# Display-Board_Rack-PDU_3_0.net
KiCad netlist of a schematic drawn in EAGLE
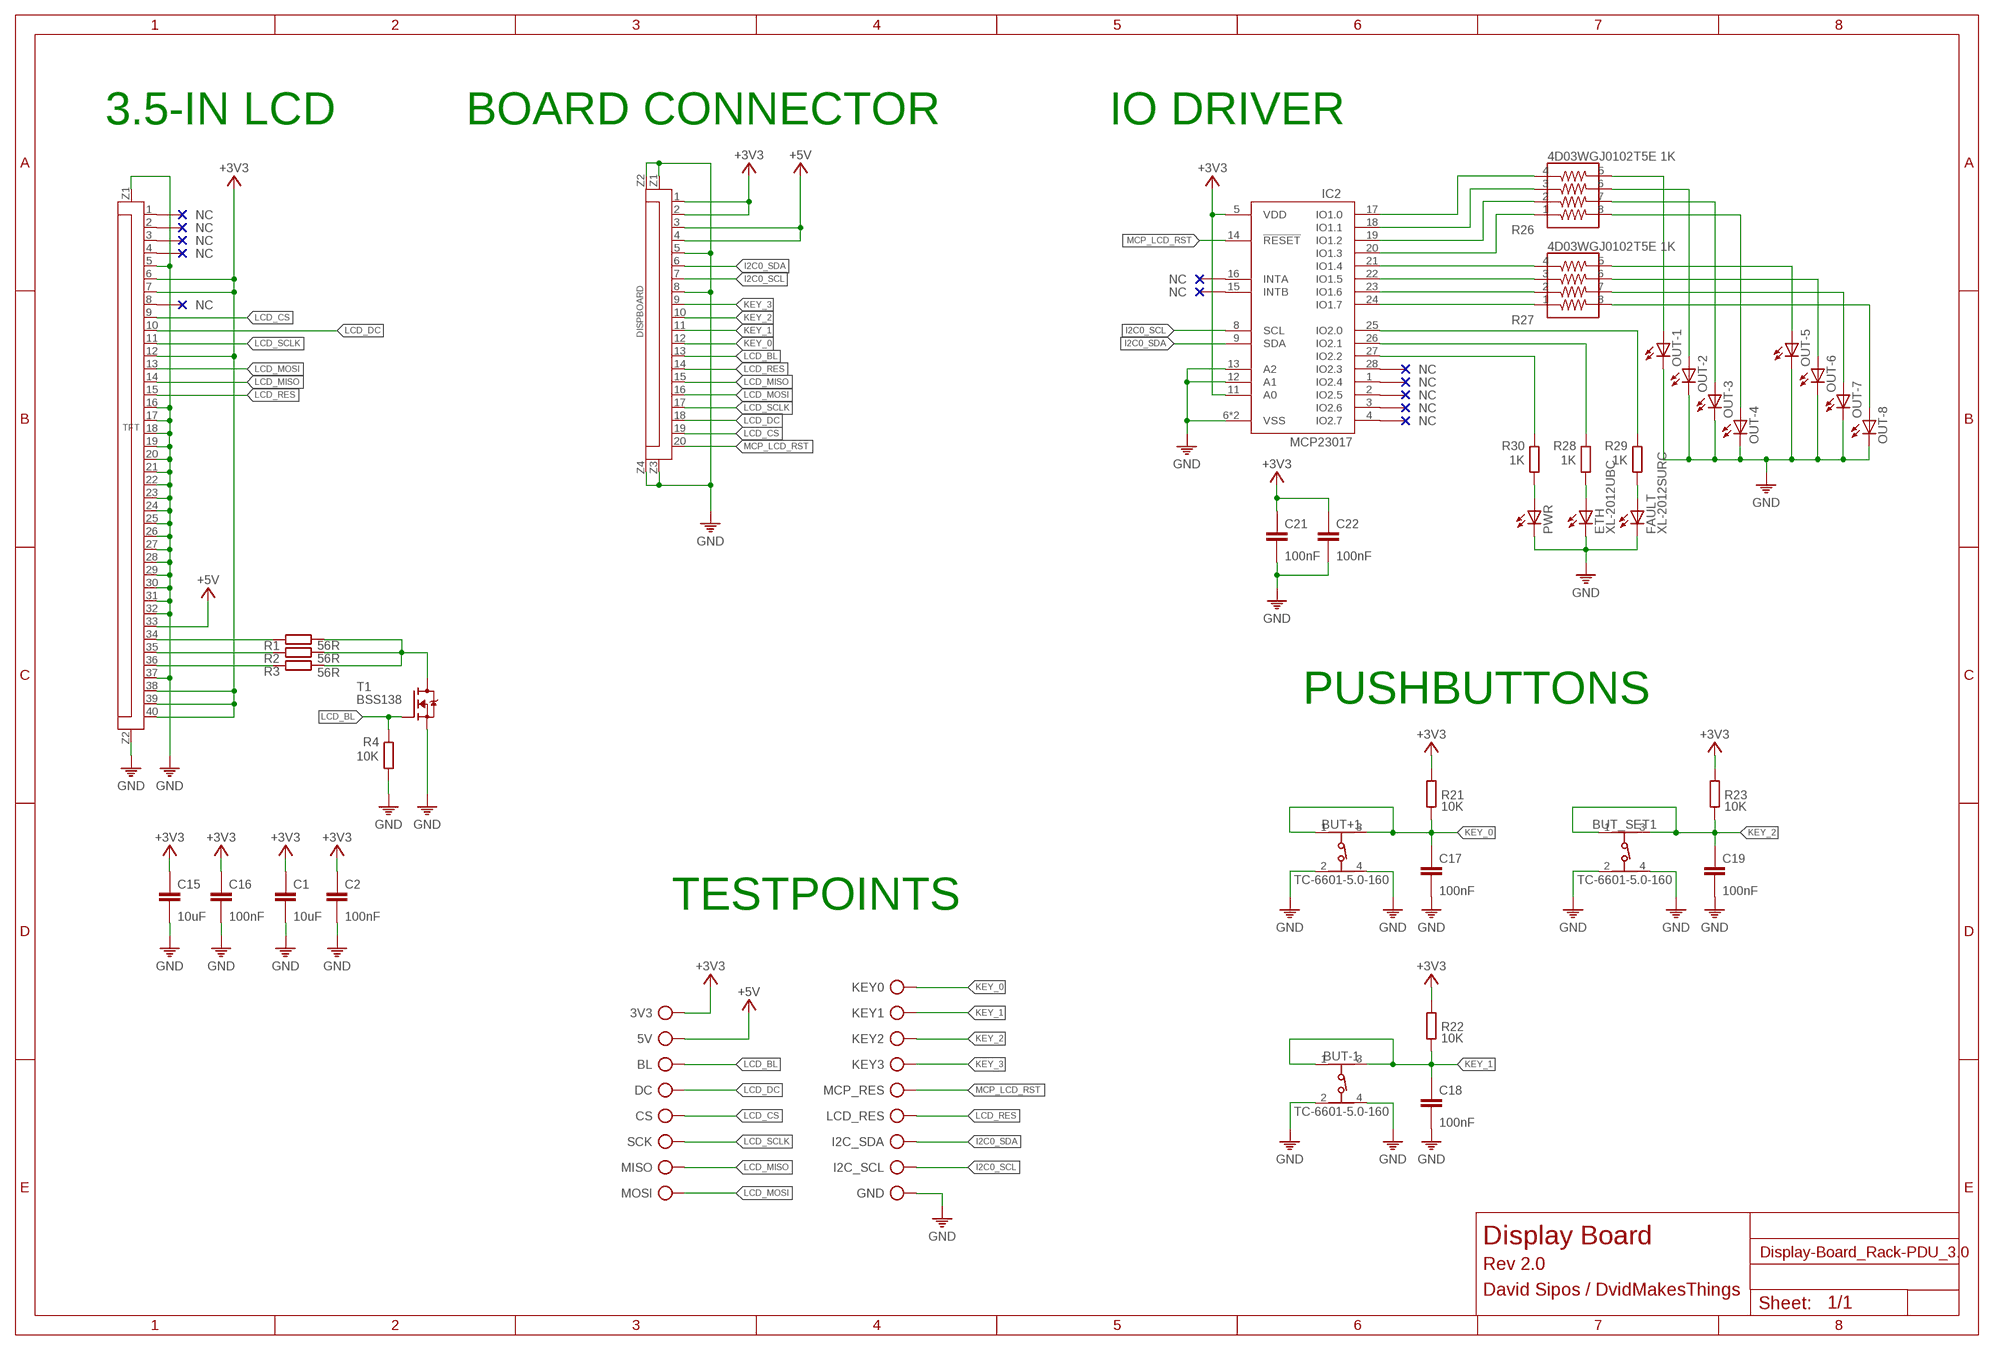
[diagram p0: schematic, sheet 1]

(export (version "E")
  (design (tool "Eeschema 10.0.6"))
  (components
    (comp (ref "3V3") (value "TP") (footprint "eagle-import:TP") (libsource (lib "eagle-import") (part "TP")))
    (comp (ref "5V") (value "TP") (footprint "eagle-import:TP") (libsource (lib "eagle-import") (part "TP")))
    (comp (ref "BL") (value "TP") (footprint "eagle-import:TP") (libsource (lib "eagle-import") (part "TP")))
    (comp (ref "BUT+1")
      (value "TC-6601-5.0-160")
      (footprint "eagle-import:430182043816")
      (libsource (lib "eagle-import") (part "430182043816"))
    )
    (comp (ref "BUT-1")
      (value "TC-6601-5.0-160")
      (footprint "eagle-import:430182043816")
      (libsource (lib "eagle-import") (part "430182043816"))
    )
    (comp (ref "BUT_SET1")
      (value "TC-6601-5.0-160")
      (footprint "eagle-import:430182043816")
      (libsource (lib "eagle-import") (part "430182043816"))
    )
    (comp (ref "C1")
      (value "10uF")
      (footprint "eagle-import:C0402")
      (libsource (lib "eagle-import") (part "C-0402"))
    )
    (comp (ref "C2")
      (value "100nF")
      (footprint "eagle-import:C0402")
      (libsource (lib "eagle-import") (part "C-0402"))
    )
    (comp (ref "C15")
      (value "10uF")
      (footprint "eagle-import:C0402")
      (libsource (lib "eagle-import") (part "C-0402"))
    )
    (comp (ref "C16")
      (value "100nF")
      (footprint "eagle-import:C0402")
      (libsource (lib "eagle-import") (part "C-0402"))
    )
    (comp (ref "C17")
      (value "100nF")
      (footprint "eagle-import:C0402")
      (libsource (lib "eagle-import") (part "C-0402"))
    )
    (comp (ref "C18")
      (value "100nF")
      (footprint "eagle-import:C0402")
      (libsource (lib "eagle-import") (part "C-0402"))
    )
    (comp (ref "C19")
      (value "100nF")
      (footprint "eagle-import:C0402")
      (libsource (lib "eagle-import") (part "C-0402"))
    )
    (comp (ref "C21")
      (value "100nF")
      (footprint "eagle-import:C0402")
      (libsource (lib "eagle-import") (part "C-0402"))
    )
    (comp (ref "C22")
      (value "100nF")
      (footprint "eagle-import:C0402")
      (libsource (lib "eagle-import") (part "C-0402"))
    )
    (comp (ref "CS") (value "TP") (footprint "eagle-import:TP") (libsource (lib "eagle-import") (part "TP")))
    (comp (ref "DC") (value "TP") (footprint "eagle-import:TP") (libsource (lib "eagle-import") (part "TP")))
    (comp (ref "DISPBOARD")
      (value "FPC20-H")
      (footprint "eagle-import:FPC20")
      (libsource (lib "eagle-import") (part "FPC20-H"))
    )
    (comp (ref "ETH")
      (value "XL-2012UBC")
      (footprint "eagle-import:CHIP-LED0805")
      (libsource (lib "eagle-import") (part "LEDCHIP-LED0805"))
    )
    (comp (ref "FAULT")
      (value "XL-2012SURC")
      (footprint "eagle-import:CHIP-LED0805")
      (libsource (lib "eagle-import") (part "LEDCHIP-LED0805"))
    )
    (comp (ref "GND") (value "TP") (footprint "eagle-import:TP") (libsource (lib "eagle-import") (part "TP")))
    (comp (ref "I2C_SCL")
      (value "TP")
      (footprint "eagle-import:TP")
      (libsource (lib "eagle-import") (part "TP"))
    )
    (comp (ref "I2C_SDA")
      (value "TP")
      (footprint "eagle-import:TP")
      (libsource (lib "eagle-import") (part "TP"))
    )
    (comp (ref "IC2")
      (value "MCP23017-E/ML")
      (footprint "eagle-import:QFN28[6X6]ML")
      (libsource (lib "eagle-import") (part "MCP23017-E/ML"))
    )
    (comp (ref "KEY0")
      (value "TP")
      (footprint "eagle-import:TP")
      (libsource (lib "eagle-import") (part "TP"))
    )
    (comp (ref "KEY1")
      (value "TP")
      (footprint "eagle-import:TP")
      (libsource (lib "eagle-import") (part "TP"))
    )
    (comp (ref "KEY2")
      (value "TP")
      (footprint "eagle-import:TP")
      (libsource (lib "eagle-import") (part "TP"))
    )
    (comp (ref "KEY3")
      (value "TP")
      (footprint "eagle-import:TP")
      (libsource (lib "eagle-import") (part "TP"))
    )
    (comp (ref "LCD_RES")
      (value "TP")
      (footprint "eagle-import:TP")
      (libsource (lib "eagle-import") (part "TP"))
    )
    (comp (ref "MCP_RES")
      (value "TP")
      (footprint "eagle-import:TP")
      (libsource (lib "eagle-import") (part "TP"))
    )
    (comp (ref "MISO")
      (value "TP")
      (footprint "eagle-import:TP")
      (libsource (lib "eagle-import") (part "TP"))
    )
    (comp (ref "MOSI")
      (value "TP")
      (footprint "eagle-import:TP")
      (libsource (lib "eagle-import") (part "TP"))
    )
    (comp (ref "OUT-1")
      (value "LEDCHIP-LED0805")
      (footprint "eagle-import:CHIP-LED0805")
      (libsource (lib "eagle-import") (part "LEDCHIP-LED0805"))
    )
    (comp (ref "OUT-2")
      (value "LEDCHIP-LED0805")
      (footprint "eagle-import:CHIP-LED0805")
      (libsource (lib "eagle-import") (part "LEDCHIP-LED0805"))
    )
    (comp (ref "OUT-3")
      (value "LEDCHIP-LED0805")
      (footprint "eagle-import:CHIP-LED0805")
      (libsource (lib "eagle-import") (part "LEDCHIP-LED0805"))
    )
    (comp (ref "OUT-4")
      (value "LEDCHIP-LED0805")
      (footprint "eagle-import:CHIP-LED0805")
      (libsource (lib "eagle-import") (part "LEDCHIP-LED0805"))
    )
    (comp (ref "OUT-5")
      (value "LEDCHIP-LED0805")
      (footprint "eagle-import:CHIP-LED0805")
      (libsource (lib "eagle-import") (part "LEDCHIP-LED0805"))
    )
    (comp (ref "OUT-6")
      (value "LEDCHIP-LED0805")
      (footprint "eagle-import:CHIP-LED0805")
      (libsource (lib "eagle-import") (part "LEDCHIP-LED0805"))
    )
    (comp (ref "OUT-7")
      (value "LEDCHIP-LED0805")
      (footprint "eagle-import:CHIP-LED0805")
      (libsource (lib "eagle-import") (part "LEDCHIP-LED0805"))
    )
    (comp (ref "OUT-8")
      (value "LEDCHIP-LED0805")
      (footprint "eagle-import:CHIP-LED0805")
      (libsource (lib "eagle-import") (part "LEDCHIP-LED0805"))
    )
    (comp (ref "PWR")
      (value "LEDCHIP-LED0805")
      (footprint "eagle-import:CHIP-LED0805")
      (libsource (lib "eagle-import") (part "LEDCHIP-LED0805"))
    )
    (comp (ref "R1")
      (value "56R")
      (footprint "eagle-import:0402")
      (libsource (lib "eagle-import") (part "R0402"))
    )
    (comp (ref "R2")
      (value "56R")
      (footprint "eagle-import:0402")
      (libsource (lib "eagle-import") (part "R0402"))
    )
    (comp (ref "R3")
      (value "56R")
      (footprint "eagle-import:0402")
      (libsource (lib "eagle-import") (part "R0402"))
    )
    (comp (ref "R4")
      (value "10K")
      (footprint "eagle-import:0402")
      (libsource (lib "eagle-import") (part "R0402"))
    )
    (comp (ref "R21")
      (value "10K")
      (footprint "eagle-import:0402")
      (libsource (lib "eagle-import") (part "R0402"))
    )
    (comp (ref "R22")
      (value "10K")
      (footprint "eagle-import:0402")
      (libsource (lib "eagle-import") (part "R0402"))
    )
    (comp (ref "R23")
      (value "10K")
      (footprint "eagle-import:0402")
      (libsource (lib "eagle-import") (part "R0402"))
    )
    (comp (ref "R26")
      (value "4D03WGJ0102T5E 1K")
      (footprint "eagle-import:742C083103JP")
      (fields
        (field (name "MANUFACTURER") "CTS Resistor Products")
        (field (name "MPN") "742C083103JP")
        (field (name "CREATED_BY") "PCBLayout.com")
      )
      (libsource (lib "eagle-import") (part "742C083103JP"))
    )
    (comp (ref "R27")
      (value "4D03WGJ0102T5E 1K")
      (footprint "eagle-import:742C083103JP")
      (fields
        (field (name "MANUFACTURER") "CTS Resistor Products")
        (field (name "MPN") "742C083103JP")
        (field (name "CREATED_BY") "PCBLayout.com")
      )
      (libsource (lib "eagle-import") (part "742C083103JP"))
    )
    (comp (ref "R28")
      (value "1K")
      (footprint "eagle-import:0402")
      (libsource (lib "eagle-import") (part "R0402"))
    )
    (comp (ref "R29")
      (value "1K")
      (footprint "eagle-import:0402")
      (libsource (lib "eagle-import") (part "R0402"))
    )
    (comp (ref "R30")
      (value "1K")
      (footprint "eagle-import:0402")
      (libsource (lib "eagle-import") (part "R0402"))
    )
    (comp (ref "SCK") (value "TP") (footprint "eagle-import:TP") (libsource (lib "eagle-import") (part "TP")))
    (comp (ref "T1")
      (value "BSS138")
      (footprint "eagle-import:SOT23")
      (libsource (lib "eagle-import") (part "BSS138"))
    )
    (comp (ref "TFT")
      (value "FPC40-HD")
      (footprint "eagle-import:FPC40_3.5TFT")
      (libsource (lib "eagle-import") (part "FPC40-HD"))
    )
  )
  (nets
    (net (code "1") (name "+3V3") (class "Default")
      (node (ref "3V3") (pin "TP") (pinfunction "P$1_TP") (pintype "bidirectional"))
      (node (ref "C1") (pin "1") (pinfunction "1_1") (pintype "passive"))
      (node (ref "C15") (pin "1") (pinfunction "1_1") (pintype "passive"))
      (node (ref "C16") (pin "1") (pinfunction "1_1") (pintype "passive"))
      (node (ref "C2") (pin "1") (pinfunction "1_1") (pintype "passive"))
      (node (ref "C21") (pin "1") (pinfunction "1_1") (pintype "passive"))
      (node (ref "C22") (pin "1") (pinfunction "1_1") (pintype "passive"))
      (node (ref "DISPBOARD") (pin "1") (pinfunction "1_1") (pintype "bidirectional"))
      (node (ref "DISPBOARD") (pin "2") (pinfunction "2_2") (pintype "bidirectional"))
      (node (ref "IC2") (pin "11") (pinfunction "A0_11") (pintype "bidirectional"))
      (node (ref "IC2") (pin "5") (pinfunction "VDD_5") (pintype "bidirectional"))
      (node (ref "R21") (pin "1") (pinfunction "1_1") (pintype "passive"))
      (node (ref "R22") (pin "1") (pinfunction "1_1") (pintype "passive"))
      (node (ref "R23") (pin "1") (pinfunction "1_1") (pintype "passive"))
      (node (ref "TFT") (pin "12") (pinfunction "12_12") (pintype "bidirectional"))
      (node (ref "TFT") (pin "38") (pinfunction "38_38") (pintype "bidirectional"))
      (node (ref "TFT") (pin "39") (pinfunction "39_39") (pintype "bidirectional"))
      (node (ref "TFT") (pin "40") (pinfunction "40_40") (pintype "bidirectional"))
      (node (ref "TFT") (pin "6") (pinfunction "6_6") (pintype "bidirectional"))
      (node (ref "TFT") (pin "7") (pinfunction "7_7") (pintype "bidirectional"))
    )
    (net (code "2") (name "+5V") (class "Default")
      (node (ref "5V") (pin "TP") (pinfunction "P$1_TP") (pintype "bidirectional"))
      (node (ref "DISPBOARD") (pin "3") (pinfunction "3_3") (pintype "bidirectional"))
      (node (ref "DISPBOARD") (pin "4") (pinfunction "4_4") (pintype "bidirectional"))
      (node (ref "TFT") (pin "33") (pinfunction "33_33") (pintype "bidirectional"))
    )
    (net (code "3") (name "GND") (class "Default")
      (node (ref "BUT+1") (pin "2") (pinfunction "2_2") (pintype "passive"))
      (node (ref "BUT+1") (pin "4") (pinfunction "4_4") (pintype "passive"))
      (node (ref "BUT-1") (pin "2") (pinfunction "2_2") (pintype "passive"))
      (node (ref "BUT-1") (pin "4") (pinfunction "4_4") (pintype "passive"))
      (node (ref "BUT_SET1") (pin "2") (pinfunction "2_2") (pintype "passive"))
      (node (ref "BUT_SET1") (pin "4") (pinfunction "4_4") (pintype "passive"))
      (node (ref "C1") (pin "2") (pinfunction "2_2") (pintype "passive"))
      (node (ref "C15") (pin "2") (pinfunction "2_2") (pintype "passive"))
      (node (ref "C16") (pin "2") (pinfunction "2_2") (pintype "passive"))
      (node (ref "C17") (pin "2") (pinfunction "2_2") (pintype "passive"))
      (node (ref "C18") (pin "2") (pinfunction "2_2") (pintype "passive"))
      (node (ref "C19") (pin "2") (pinfunction "2_2") (pintype "passive"))
      (node (ref "C2") (pin "2") (pinfunction "2_2") (pintype "passive"))
      (node (ref "C21") (pin "2") (pinfunction "2_2") (pintype "passive"))
      (node (ref "C22") (pin "2") (pinfunction "2_2") (pintype "passive"))
      (node (ref "DISPBOARD") (pin "5") (pinfunction "5_5") (pintype "bidirectional"))
      (node (ref "DISPBOARD") (pin "8") (pinfunction "8_8") (pintype "bidirectional"))
      (node (ref "DISPBOARD") (pin "Z1") (pinfunction "Z1_Z1") (pintype "bidirectional"))
      (node (ref "DISPBOARD") (pin "Z2") (pinfunction "Z2_Z2") (pintype "bidirectional"))
      (node (ref "DISPBOARD") (pin "Z3") (pinfunction "Z3_Z3") (pintype "bidirectional"))
      (node (ref "DISPBOARD") (pin "Z4") (pinfunction "Z4_Z4") (pintype "bidirectional"))
      (node (ref "ETH") (pin "C") (pinfunction "C_C") (pintype "passive"))
      (node (ref "FAULT") (pin "C") (pinfunction "C_C") (pintype "passive"))
      (node (ref "GND") (pin "TP") (pinfunction "P$1_TP") (pintype "bidirectional"))
      (node (ref "IC2") (pin "12") (pinfunction "A1_12") (pintype "bidirectional"))
      (node (ref "IC2") (pin "13") (pinfunction "A2_13") (pintype "bidirectional"))
      (node (ref "IC2") (pin "6") (pinfunction "VSS_6") (pintype "bidirectional"))
      (node (ref "IC2") (pin "PAD") (pinfunction "VSS_PAD") (pintype "bidirectional"))
      (node (ref "OUT-1") (pin "C") (pinfunction "C_C") (pintype "passive"))
      (node (ref "OUT-2") (pin "C") (pinfunction "C_C") (pintype "passive"))
      (node (ref "OUT-3") (pin "C") (pinfunction "C_C") (pintype "passive"))
      (node (ref "OUT-4") (pin "C") (pinfunction "C_C") (pintype "passive"))
      (node (ref "OUT-5") (pin "C") (pinfunction "C_C") (pintype "passive"))
      (node (ref "OUT-6") (pin "C") (pinfunction "C_C") (pintype "passive"))
      (node (ref "OUT-7") (pin "C") (pinfunction "C_C") (pintype "passive"))
      (node (ref "OUT-8") (pin "C") (pinfunction "C_C") (pintype "passive"))
      (node (ref "PWR") (pin "C") (pinfunction "C_C") (pintype "passive"))
      (node (ref "R4") (pin "2") (pinfunction "2_2") (pintype "passive"))
      (node (ref "T1") (pin "2") (pinfunction "S_2") (pintype "passive"))
      (node (ref "TFT") (pin "16") (pinfunction "16_16") (pintype "bidirectional"))
      (node (ref "TFT") (pin "17") (pinfunction "17_17") (pintype "bidirectional"))
      (node (ref "TFT") (pin "18") (pinfunction "18_18") (pintype "bidirectional"))
      (node (ref "TFT") (pin "19") (pinfunction "19_19") (pintype "bidirectional"))
      (node (ref "TFT") (pin "20") (pinfunction "20_20") (pintype "bidirectional"))
      (node (ref "TFT") (pin "21") (pinfunction "21_21") (pintype "bidirectional"))
      (node (ref "TFT") (pin "22") (pinfunction "22_22") (pintype "bidirectional"))
      (node (ref "TFT") (pin "23") (pinfunction "23_23") (pintype "bidirectional"))
      (node (ref "TFT") (pin "24") (pinfunction "24_24") (pintype "bidirectional"))
      (node (ref "TFT") (pin "25") (pinfunction "25_25") (pintype "bidirectional"))
      (node (ref "TFT") (pin "26") (pinfunction "26_26") (pintype "bidirectional"))
      (node (ref "TFT") (pin "27") (pinfunction "27_27") (pintype "bidirectional"))
      (node (ref "TFT") (pin "28") (pinfunction "28_28") (pintype "bidirectional"))
      (node (ref "TFT") (pin "29") (pinfunction "29_29") (pintype "bidirectional"))
      (node (ref "TFT") (pin "30") (pinfunction "30_30") (pintype "bidirectional"))
      (node (ref "TFT") (pin "31") (pinfunction "31_31") (pintype "bidirectional"))
      (node (ref "TFT") (pin "32") (pinfunction "32_32") (pintype "bidirectional"))
      (node (ref "TFT") (pin "37") (pinfunction "37_37") (pintype "bidirectional"))
      (node (ref "TFT") (pin "5") (pinfunction "5_5") (pintype "bidirectional"))
      (node (ref "TFT") (pin "Z1") (pinfunction "Z1_Z1") (pintype "bidirectional"))
      (node (ref "TFT") (pin "Z2") (pinfunction "Z2_Z2") (pintype "bidirectional"))
    )
    (net (code "4") (name "I2C0_SCL") (class "Default")
      (node (ref "DISPBOARD") (pin "7") (pinfunction "7_7") (pintype "bidirectional"))
      (node (ref "I2C_SCL") (pin "TP") (pinfunction "P$1_TP") (pintype "bidirectional"))
      (node (ref "IC2") (pin "8") (pinfunction "SCL_8") (pintype "bidirectional"))
    )
    (net (code "5") (name "I2C0_SDA") (class "Default")
      (node (ref "DISPBOARD") (pin "6") (pinfunction "6_6") (pintype "bidirectional"))
      (node (ref "I2C_SDA") (pin "TP") (pinfunction "P$1_TP") (pintype "bidirectional"))
      (node (ref "IC2") (pin "9") (pinfunction "SDA_9") (pintype "bidirectional"))
    )
    (net (code "6") (name "KEY_0") (class "Default")
      (node (ref "BUT+1") (pin "1") (pinfunction "1_1") (pintype "passive"))
      (node (ref "BUT+1") (pin "3") (pinfunction "3_3") (pintype "passive"))
      (node (ref "C17") (pin "1") (pinfunction "1_1") (pintype "passive"))
      (node (ref "DISPBOARD") (pin "12") (pinfunction "12_12") (pintype "bidirectional"))
      (node (ref "KEY0") (pin "TP") (pinfunction "P$1_TP") (pintype "bidirectional"))
      (node (ref "R21") (pin "2") (pinfunction "2_2") (pintype "passive"))
    )
    (net (code "7") (name "KEY_1") (class "Default")
      (node (ref "BUT-1") (pin "1") (pinfunction "1_1") (pintype "passive"))
      (node (ref "BUT-1") (pin "3") (pinfunction "3_3") (pintype "passive"))
      (node (ref "C18") (pin "1") (pinfunction "1_1") (pintype "passive"))
      (node (ref "DISPBOARD") (pin "11") (pinfunction "11_11") (pintype "bidirectional"))
      (node (ref "KEY1") (pin "TP") (pinfunction "P$1_TP") (pintype "bidirectional"))
      (node (ref "R22") (pin "2") (pinfunction "2_2") (pintype "passive"))
    )
    (net (code "8") (name "KEY_2") (class "Default")
      (node (ref "BUT_SET1") (pin "1") (pinfunction "1_1") (pintype "passive"))
      (node (ref "BUT_SET1") (pin "3") (pinfunction "3_3") (pintype "passive"))
      (node (ref "C19") (pin "1") (pinfunction "1_1") (pintype "passive"))
      (node (ref "DISPBOARD") (pin "10") (pinfunction "10_10") (pintype "bidirectional"))
      (node (ref "KEY2") (pin "TP") (pinfunction "P$1_TP") (pintype "bidirectional"))
      (node (ref "R23") (pin "2") (pinfunction "2_2") (pintype "passive"))
    )
    (net (code "9") (name "KEY_3") (class "Default")
      (node (ref "DISPBOARD") (pin "9") (pinfunction "9_9") (pintype "bidirectional"))
      (node (ref "KEY3") (pin "TP") (pinfunction "P$1_TP") (pintype "bidirectional"))
    )
    (net (code "10") (name "LCD_BL") (class "Default")
      (node (ref "BL") (pin "TP") (pinfunction "P$1_TP") (pintype "bidirectional"))
      (node (ref "DISPBOARD") (pin "13") (pinfunction "13_13") (pintype "bidirectional"))
      (node (ref "R4") (pin "1") (pinfunction "1_1") (pintype "passive"))
      (node (ref "T1") (pin "1") (pinfunction "G_1") (pintype "passive"))
    )
    (net (code "11") (name "LCD_CS") (class "Default")
      (node (ref "CS") (pin "TP") (pinfunction "P$1_TP") (pintype "bidirectional"))
      (node (ref "DISPBOARD") (pin "19") (pinfunction "19_19") (pintype "bidirectional"))
      (node (ref "TFT") (pin "9") (pinfunction "9_9") (pintype "bidirectional"))
    )
    (net (code "12") (name "LCD_DC") (class "Default")
      (node (ref "DC") (pin "TP") (pinfunction "P$1_TP") (pintype "bidirectional"))
      (node (ref "DISPBOARD") (pin "18") (pinfunction "18_18") (pintype "bidirectional"))
      (node (ref "TFT") (pin "10") (pinfunction "10_10") (pintype "bidirectional"))
    )
    (net (code "13") (name "LCD_MISO") (class "Default")
      (node (ref "DISPBOARD") (pin "15") (pinfunction "15_15") (pintype "bidirectional"))
      (node (ref "MISO") (pin "TP") (pinfunction "P$1_TP") (pintype "bidirectional"))
      (node (ref "TFT") (pin "14") (pinfunction "14_14") (pintype "bidirectional"))
    )
    (net (code "14") (name "LCD_MOSI") (class "Default")
      (node (ref "DISPBOARD") (pin "16") (pinfunction "16_16") (pintype "bidirectional"))
      (node (ref "MOSI") (pin "TP") (pinfunction "P$1_TP") (pintype "bidirectional"))
      (node (ref "TFT") (pin "13") (pinfunction "13_13") (pintype "bidirectional"))
    )
    (net (code "15") (name "LCD_RES") (class "Default")
      (node (ref "DISPBOARD") (pin "14") (pinfunction "14_14") (pintype "bidirectional"))
      (node (ref "LCD_RES") (pin "TP") (pinfunction "P$1_TP") (pintype "bidirectional"))
      (node (ref "TFT") (pin "15") (pinfunction "15_15") (pintype "bidirectional"))
    )
    (net (code "16") (name "LCD_SCLK") (class "Default")
      (node (ref "DISPBOARD") (pin "17") (pinfunction "17_17") (pintype "bidirectional"))
      (node (ref "SCK") (pin "TP") (pinfunction "P$1_TP") (pintype "bidirectional"))
      (node (ref "TFT") (pin "11") (pinfunction "11_11") (pintype "bidirectional"))
    )
    (net (code "17") (name "MCP_LCD_RST") (class "Default")
      (node (ref "DISPBOARD") (pin "20") (pinfunction "20_20") (pintype "bidirectional"))
      (node (ref "IC2") (pin "14") (pinfunction "~{RESET}_14") (pintype "bidirectional"))
      (node (ref "MCP_RES") (pin "TP") (pinfunction "P$1_TP") (pintype "bidirectional"))
    )
    (net (code "18") (name "Net-(ETH-PadA)") (class "Default")
      (node (ref "ETH") (pin "A") (pinfunction "A_A") (pintype "passive"))
      (node (ref "R28") (pin "2") (pinfunction "2_2") (pintype "passive"))
    )
    (net (code "19") (name "Net-(FAULT-PadA)") (class "Default")
      (node (ref "FAULT") (pin "A") (pinfunction "A_A") (pintype "passive"))
      (node (ref "R29") (pin "2") (pinfunction "2_2") (pintype "passive"))
    )
    (net (code "20") (name "Net-(IC2-IO1.0)") (class "Default")
      (node (ref "IC2") (pin "17") (pinfunction "IO1.0_17") (pintype "bidirectional"))
      (node (ref "R26") (pin "4") (pinfunction "4_4") (pintype "passive"))
    )
    (net (code "21") (name "Net-(IC2-IO1.1)") (class "Default")
      (node (ref "IC2") (pin "18") (pinfunction "IO1.1_18") (pintype "bidirectional"))
      (node (ref "R26") (pin "3") (pinfunction "3_3") (pintype "passive"))
    )
    (net (code "22") (name "Net-(IC2-IO1.2)") (class "Default")
      (node (ref "IC2") (pin "19") (pinfunction "IO1.2_19") (pintype "bidirectional"))
      (node (ref "R26") (pin "2") (pinfunction "2_2") (pintype "passive"))
    )
    (net (code "23") (name "Net-(IC2-IO1.3)") (class "Default")
      (node (ref "IC2") (pin "20") (pinfunction "IO1.3_20") (pintype "bidirectional"))
      (node (ref "R26") (pin "1") (pinfunction "1_1") (pintype "passive"))
    )
    (net (code "24") (name "Net-(IC2-IO1.4)") (class "Default")
      (node (ref "IC2") (pin "21") (pinfunction "IO1.4_21") (pintype "bidirectional"))
      (node (ref "R27") (pin "4") (pinfunction "4_4") (pintype "passive"))
    )
    (net (code "25") (name "Net-(IC2-IO1.5)") (class "Default")
      (node (ref "IC2") (pin "22") (pinfunction "IO1.5_22") (pintype "bidirectional"))
      (node (ref "R27") (pin "3") (pinfunction "3_3") (pintype "passive"))
    )
    (net (code "26") (name "Net-(IC2-IO1.6)") (class "Default")
      (node (ref "IC2") (pin "23") (pinfunction "IO1.6_23") (pintype "bidirectional"))
      (node (ref "R27") (pin "2") (pinfunction "2_2") (pintype "passive"))
    )
    (net (code "27") (name "Net-(IC2-IO1.7)") (class "Default")
      (node (ref "IC2") (pin "24") (pinfunction "IO1.7_24") (pintype "bidirectional"))
      (node (ref "R27") (pin "1") (pinfunction "1_1") (pintype "passive"))
    )
    (net (code "28") (name "Net-(IC2-IO2.0)") (class "Default")
      (node (ref "IC2") (pin "25") (pinfunction "IO2.0_25") (pintype "bidirectional"))
      (node (ref "R29") (pin "1") (pinfunction "1_1") (pintype "passive"))
    )
    (net (code "29") (name "Net-(IC2-IO2.1)") (class "Default")
      (node (ref "IC2") (pin "26") (pinfunction "IO2.1_26") (pintype "bidirectional"))
      (node (ref "R28") (pin "1") (pinfunction "1_1") (pintype "passive"))
    )
    (net (code "30") (name "Net-(IC2-IO2.2)") (class "Default")
      (node (ref "IC2") (pin "27") (pinfunction "IO2.2_27") (pintype "bidirectional"))
      (node (ref "R30") (pin "1") (pinfunction "1_1") (pintype "passive"))
    )
    (net (code "31") (name "Net-(OUT-1-PadA)") (class "Default")
      (node (ref "OUT-1") (pin "A") (pinfunction "A_A") (pintype "passive"))
      (node (ref "R26") (pin "5") (pinfunction "5_5") (pintype "passive"))
    )
    (net (code "32") (name "Net-(OUT-2-PadA)") (class "Default")
      (node (ref "OUT-2") (pin "A") (pinfunction "A_A") (pintype "passive"))
      (node (ref "R26") (pin "6") (pinfunction "6_6") (pintype "passive"))
    )
    (net (code "33") (name "Net-(OUT-3-PadA)") (class "Default")
      (node (ref "OUT-3") (pin "A") (pinfunction "A_A") (pintype "passive"))
      (node (ref "R26") (pin "7") (pinfunction "7_7") (pintype "passive"))
    )
    (net (code "34") (name "Net-(OUT-4-PadA)") (class "Default")
      (node (ref "OUT-4") (pin "A") (pinfunction "A_A") (pintype "passive"))
      (node (ref "R26") (pin "8") (pinfunction "8_8") (pintype "passive"))
    )
    (net (code "35") (name "Net-(OUT-5-PadA)") (class "Default")
      (node (ref "OUT-5") (pin "A") (pinfunction "A_A") (pintype "passive"))
      (node (ref "R27") (pin "5") (pinfunction "5_5") (pintype "passive"))
    )
    (net (code "36") (name "Net-(OUT-6-PadA)") (class "Default")
      (node (ref "OUT-6") (pin "A") (pinfunction "A_A") (pintype "passive"))
      (node (ref "R27") (pin "6") (pinfunction "6_6") (pintype "passive"))
    )
    (net (code "37") (name "Net-(OUT-7-PadA)") (class "Default")
      (node (ref "OUT-7") (pin "A") (pinfunction "A_A") (pintype "passive"))
      (node (ref "R27") (pin "7") (pinfunction "7_7") (pintype "passive"))
    )
    (net (code "38") (name "Net-(OUT-8-PadA)") (class "Default")
      (node (ref "OUT-8") (pin "A") (pinfunction "A_A") (pintype "passive"))
      (node (ref "R27") (pin "8") (pinfunction "8_8") (pintype "passive"))
    )
    (net (code "39") (name "Net-(PWR-PadA)") (class "Default")
      (node (ref "PWR") (pin "A") (pinfunction "A_A") (pintype "passive"))
      (node (ref "R30") (pin "2") (pinfunction "2_2") (pintype "passive"))
    )
    (net (code "40") (name "Net-(R1-Pad2)") (class "Default")
      (node (ref "R1") (pin "2") (pinfunction "2_2") (pintype "passive"))
      (node (ref "TFT") (pin "34") (pinfunction "34_34") (pintype "bidirectional"))
    )
    (net (code "41") (name "Net-(R2-Pad2)") (class "Default")
      (node (ref "R2") (pin "2") (pinfunction "2_2") (pintype "passive"))
      (node (ref "TFT") (pin "35") (pinfunction "35_35") (pintype "bidirectional"))
    )
    (net (code "42") (name "Net-(R3-Pad2)") (class "Default")
      (node (ref "R3") (pin "2") (pinfunction "2_2") (pintype "passive"))
      (node (ref "TFT") (pin "36") (pinfunction "36_36") (pintype "bidirectional"))
    )
    (net (code "43") (name "Net-(T1-D)") (class "Default")
      (node (ref "R1") (pin "1") (pinfunction "1_1") (pintype "passive"))
      (node (ref "R2") (pin "1") (pinfunction "1_1") (pintype "passive"))
      (node (ref "R3") (pin "1") (pinfunction "1_1") (pintype "passive"))
      (node (ref "T1") (pin "3") (pinfunction "D_3") (pintype "passive"))
    )
    (net (code "44") (name "unconnected-(IC2-INTA-Pad16)") (class "Default")
      (node (ref "IC2") (pin "16") (pinfunction "INTA_16") (pintype "bidirectional"))
    )
    (net (code "45") (name "unconnected-(IC2-INTB-Pad15)") (class "Default")
      (node (ref "IC2") (pin "15") (pinfunction "INTB_15") (pintype "bidirectional"))
    )
    (net (code "46") (name "unconnected-(IC2-IO2.3-Pad28)") (class "Default")
      (node (ref "IC2") (pin "28") (pinfunction "IO2.3_28") (pintype "bidirectional"))
    )
    (net (code "47") (name "unconnected-(IC2-IO2.4-Pad1)") (class "Default")
      (node (ref "IC2") (pin "1") (pinfunction "IO2.4_1") (pintype "bidirectional"))
    )
    (net (code "48") (name "unconnected-(IC2-IO2.5-Pad2)") (class "Default")
      (node (ref "IC2") (pin "2") (pinfunction "IO2.5_2") (pintype "bidirectional"))
    )
    (net (code "49") (name "unconnected-(IC2-IO2.6-Pad3)") (class "Default")
      (node (ref "IC2") (pin "3") (pinfunction "IO2.6_3") (pintype "bidirectional"))
    )
    (net (code "50") (name "unconnected-(IC2-IO2.7-Pad4)") (class "Default")
      (node (ref "IC2") (pin "4") (pinfunction "IO2.7_4") (pintype "bidirectional"))
    )
    (net (code "51") (name "unconnected-(TFT-Pad1)") (class "Default")
      (node (ref "TFT") (pin "1") (pinfunction "1_1") (pintype "bidirectional"))
    )
    (net (code "52") (name "unconnected-(TFT-Pad2)") (class "Default")
      (node (ref "TFT") (pin "2") (pinfunction "2_2") (pintype "bidirectional"))
    )
    (net (code "53") (name "unconnected-(TFT-Pad3)") (class "Default")
      (node (ref "TFT") (pin "3") (pinfunction "3_3") (pintype "bidirectional"))
    )
    (net (code "54") (name "unconnected-(TFT-Pad4)") (class "Default")
      (node (ref "TFT") (pin "4") (pinfunction "4_4") (pintype "bidirectional"))
    )
    (net (code "55") (name "unconnected-(TFT-Pad8)") (class "Default")
      (node (ref "TFT") (pin "8") (pinfunction "8_8") (pintype "bidirectional"))
    )
  )
)
